# LC_LPF9.net
KiCad netlist of a schematic drawn in Altium Designer
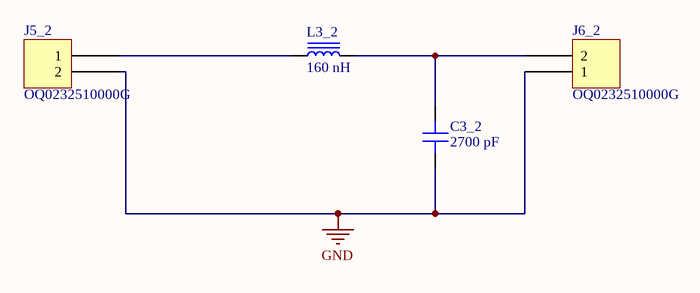
[diagram p0: LC_LPF9.SchDoc]

(export (version "E")
  (design (tool "Eeschema 10.0.6"))
  (components
    (comp (ref "C3_2")
      (value "2700 pF")
      (footprint "CAP 0603_1608")
      (description "CAP CER 2700PF 25V NP0 0603")
      (fields (field (name "PART NUMBER") "C0603C272F3GAC7867") (field (name "MANUFACTURER") "KEMET"))
      (libsource (lib "Celestial Altium Library - altium_library") (part "Capacitor"))
    )
    (comp (ref "J5_2")
      (value "OQ0232510000G")
      (footprint "FCI 06-381-2PIN")
      (description "TERM BLOCK HDR 2POS 90DEG 3.81MM")
      (fields (field (name "MANUFACTURER") "Amphenol Anytek"))
      (libsource (lib "Celestial Altium Library - altium_library") (part "2 Pin"))
    )
    (comp (ref "J6_2")
      (value "OQ0232510000G")
      (footprint "FCI 06-381-2PIN")
      (description "TERM BLOCK HDR 2POS 90DEG 3.81MM")
      (fields (field (name "MANUFACTURER") "Amphenol Anytek"))
      (libsource (lib "") (part "2 Pin_1"))
    )
    (comp (ref "L3_2")
      (value "160 nH")
      (footprint "IND 0402_1005 RF WW")
      (description "FIXED IND 160NH 480MA 330MOHM SM")
      (fields
        (field (name "PART NUMBER") "LQW15CNR16J00D")
        (field (name "MANUFACTURER") "Murata Electronics")
      )
      (libsource (lib "Celestial Altium Library - altium_library") (part "Inductor"))
    )
  )
  (nets
    (net (code "1") (name "GND") (class "Default")
      (node (ref "C3_2") (pin "1") (pinfunction "1_1") (pintype "passive"))
      (node (ref "J5_2") (pin "2") (pinfunction "2_2") (pintype "passive"))
      (node (ref "J6_2") (pin "1") (pinfunction "1_1") (pintype "passive"))
    )
    (net (code "2") (name "Net-(C3_2-Pad2)") (class "Default")
      (node (ref "C3_2") (pin "2") (pinfunction "2_2") (pintype "passive"))
      (node (ref "J6_2") (pin "2") (pinfunction "2_2") (pintype "passive"))
      (node (ref "L3_2") (pin "2") (pinfunction "2_2") (pintype "passive"))
    )
    (net (code "3") (name "Net-(J5_2-Pad1)") (class "Default")
      (node (ref "J5_2") (pin "1") (pinfunction "1_1") (pintype "passive"))
      (node (ref "L3_2") (pin "1") (pinfunction "1_1") (pintype "passive"))
    )
  )
)
